# PGS_3.net
KiCad netlist of a schematic drawn in Altium Designer
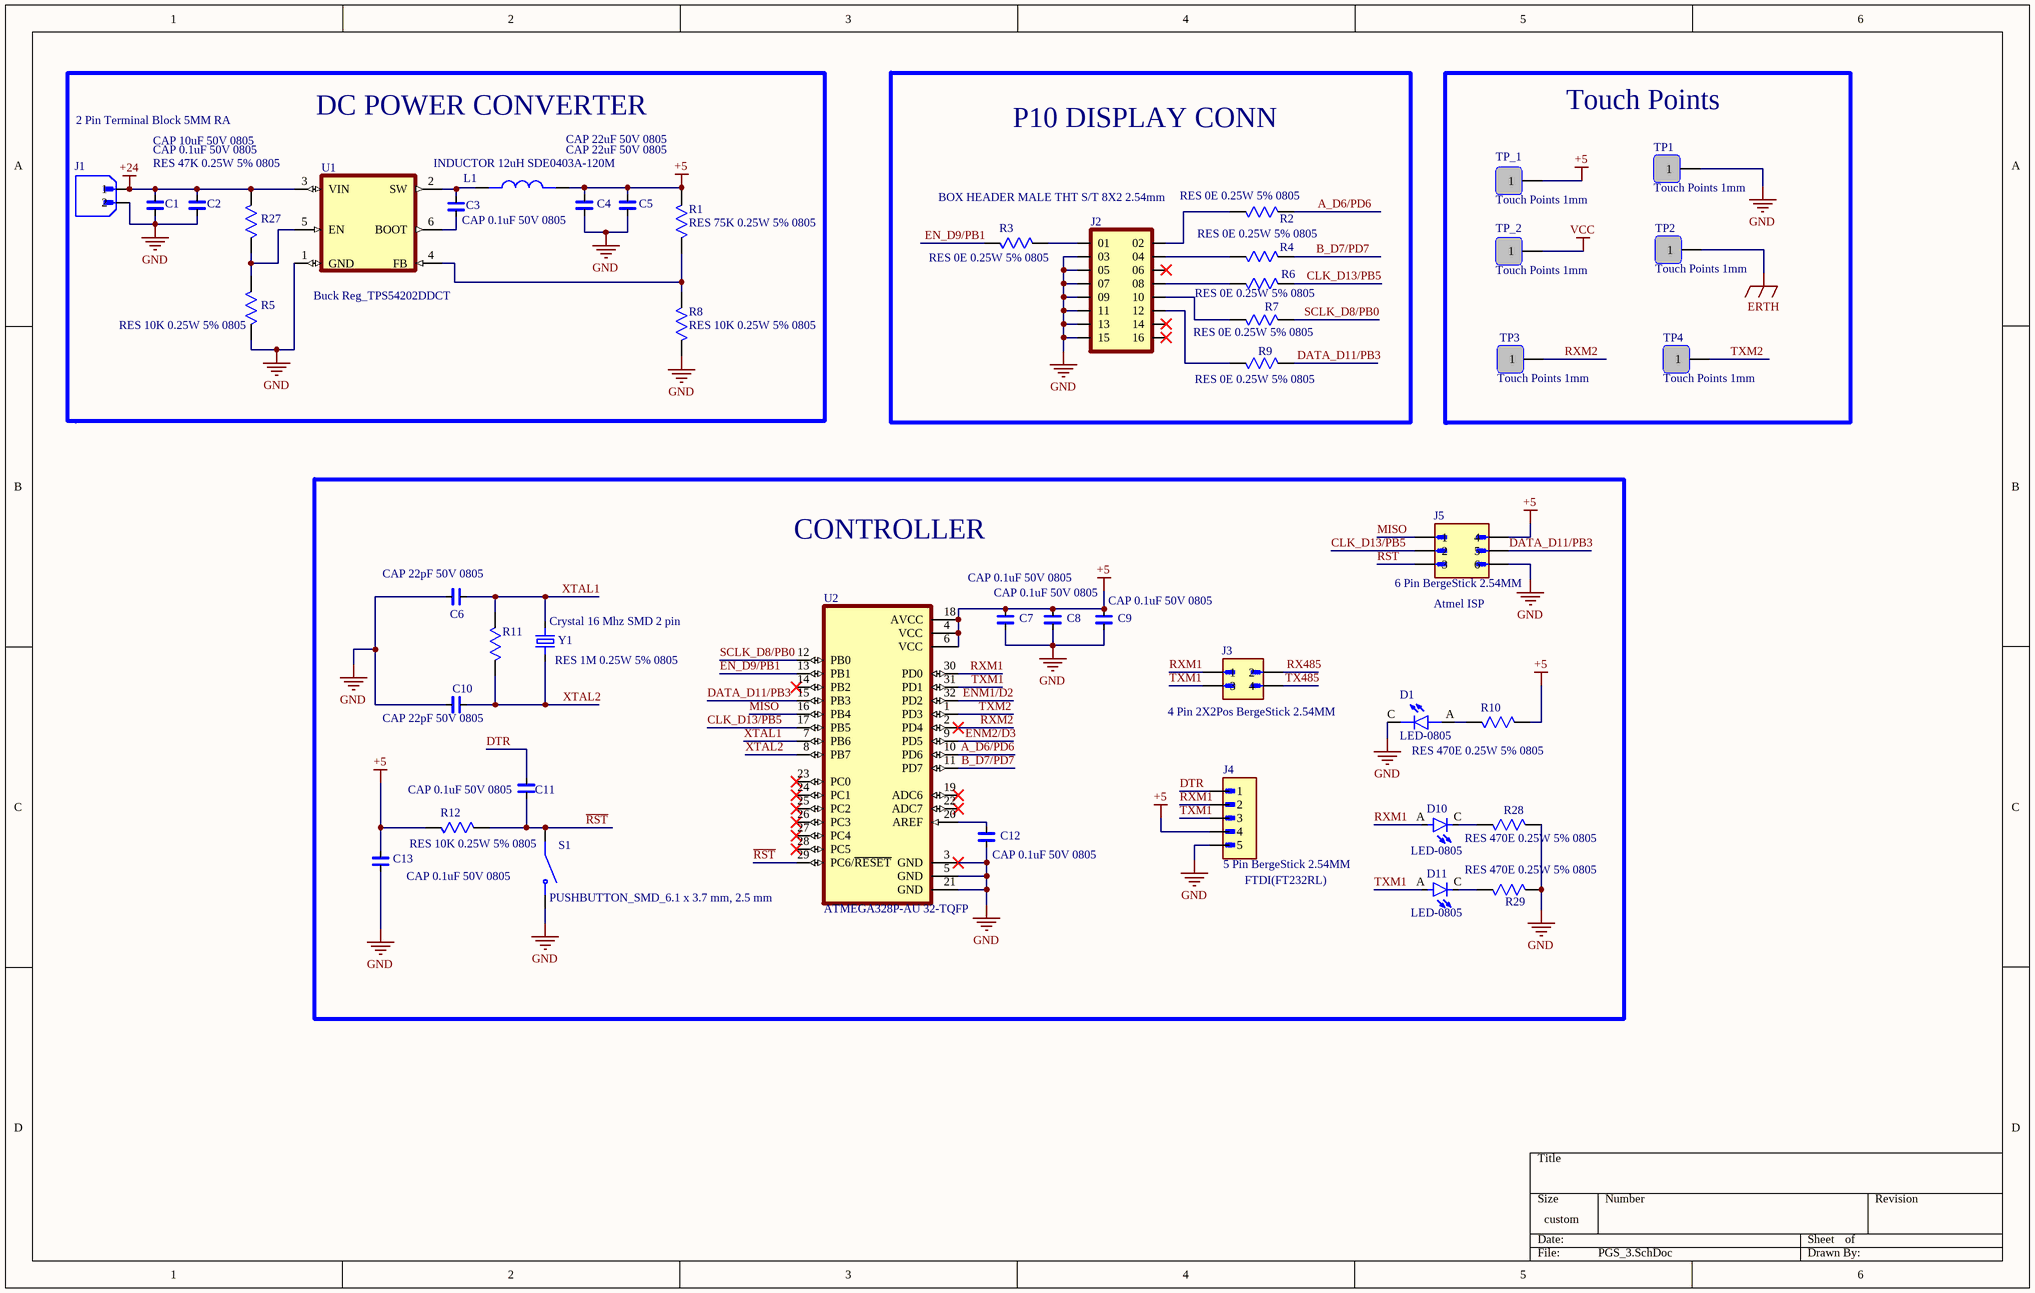
[diagram p0: PGS_3.SchDoc]

(export (version "E")
  (design (tool "Eeschema 10.0.6"))
  (components
    (comp (ref "C1")
      (value "CAP 10uF 50V 0805")
      (footprint "CAP CER 0.1uF/50V 5%")
      (description "CAP CER 0.1uF/50V  Ceramic Capacitor X7R 0805 (2012 Metric)")
      (fields (field (name "MF") "Samsung") (field (name "MP") "CL21B104KCFNNNE"))
      (libsource (lib "PGS") (part "CAP CER 0.1uF/50V 5%"))
    )
    (comp (ref "C2")
      (value "CAP 0.1uF 50V 0805")
      (footprint "CAP CER 0.1uF/50V 5%")
      (description "CAP CER 0.1uF/50V  Ceramic Capacitor X7R 0805 (2012 Metric)")
      (fields (field (name "MF") "Samsung") (field (name "MP") "CL21B104KCFNNNE"))
      (libsource (lib "PGS") (part "CAP CER 0.1uF/50V 5%"))
    )
    (comp (ref "C3")
      (value "CAP 0.1uF 50V 0805")
      (footprint "CAP CER 0.1uF/50V 5%")
      (description "CAP CER 0.1uF/50V  Ceramic Capacitor X7R 0805 (2012 Metric)")
      (fields (field (name "MF") "Samsung") (field (name "MP") "CL21B104KCFNNNE"))
      (libsource (lib "PGS") (part "CAP CER 0.1uF/50V 5%"))
    )
    (comp (ref "C4")
      (value "CAP 22uF 50V 0805")
      (footprint "CAP CER 0.1uF/50V 5%")
      (description "CAP CER 0.1uF/50V  Ceramic Capacitor X7R 0805 (2012 Metric)")
      (fields (field (name "MF") "Samsung") (field (name "MP") "CL21B104KCFNNNE"))
      (libsource (lib "PGS") (part "CAP CER 0.1uF/50V 5%"))
    )
    (comp (ref "C5")
      (value "CAP 22uF 50V 0805")
      (footprint "CAP CER 0.1uF/50V 5%")
      (description "CAP CER 0.1uF/50V  Ceramic Capacitor X7R 0805 (2012 Metric)")
      (fields (field (name "MF") "Samsung") (field (name "MP") "CL21B104KCFNNNE"))
      (libsource (lib "PGS") (part "CAP CER 0.1uF/50V 5%"))
    )
    (comp (ref "C6")
      (value "CAP 22pF 50V 0805")
      (footprint "CAP CER 0.1uF/50V 5%")
      (description "CAP CER 0.1uF/50V  Ceramic Capacitor X7R 0805 (2012 Metric)")
      (fields (field (name "MF") "Samsung") (field (name "MP") "CL21B104KCFNNNE"))
      (libsource (lib "") (part "CAP CER 0.1uF/50V 5%_1"))
    )
    (comp (ref "C7")
      (value "CAP 0.1uF 50V 0805")
      (footprint "CAP CER 0.1uF/50V 5%")
      (description "CAP CER 0.1uF/50V  Ceramic Capacitor X7R 0805 (2012 Metric)")
      (fields (field (name "MF") "Samsung") (field (name "MP") "CL21B104KCFNNNE"))
      (libsource (lib "PGS") (part "CAP CER 0.1uF/50V 5%"))
    )
    (comp (ref "C8")
      (value "CAP 0.1uF 50V 0805")
      (footprint "CAP CER 0.1uF/50V 5%")
      (description "CAP CER 0.1uF/50V  Ceramic Capacitor X7R 0805 (2012 Metric)")
      (fields (field (name "MF") "Samsung") (field (name "MP") "CL21B104KCFNNNE"))
      (libsource (lib "PGS") (part "CAP CER 0.1uF/50V 5%"))
    )
    (comp (ref "C9")
      (value "CAP 0.1uF 50V 0805")
      (footprint "CAP CER 0.1uF/50V 5%")
      (description "CAP CER 0.1uF/50V  Ceramic Capacitor X7R 0805 (2012 Metric)")
      (fields (field (name "MF") "Samsung") (field (name "MP") "CL21B104KCFNNNE"))
      (libsource (lib "PGS") (part "CAP CER 0.1uF/50V 5%"))
    )
    (comp (ref "C10")
      (value "CAP 22pF 50V 0805")
      (footprint "CAP CER 0.1uF/50V 5%")
      (description "CAP CER 0.1uF/50V  Ceramic Capacitor X7R 0805 (2012 Metric)")
      (fields (field (name "MF") "Samsung") (field (name "MP") "CL21B104KCFNNNE"))
      (libsource (lib "") (part "CAP CER 0.1uF/50V 5%_1"))
    )
    (comp (ref "C11")
      (value "CAP 0.1uF 50V 0805")
      (footprint "CAP CER 0.1uF/50V 5%")
      (description "CAP CER 0.1uF/50V  Ceramic Capacitor X7R 0805 (2012 Metric)")
      (fields (field (name "MF") "Samsung") (field (name "MP") "CL21B104KCFNNNE"))
      (libsource (lib "PGS") (part "CAP CER 0.1uF/50V 5%"))
    )
    (comp (ref "C12")
      (value "CAP 0.1uF 50V 0805")
      (footprint "CAP CER 0.1uF/50V 5%")
      (description "CAP CER 0.1uF/50V  Ceramic Capacitor X7R 0805 (2012 Metric)")
      (fields (field (name "MF") "Samsung") (field (name "MP") "CL21B104KCFNNNE"))
      (libsource (lib "PGS") (part "CAP CER 0.1uF/50V 5%"))
    )
    (comp (ref "C13")
      (value "CAP 0.1uF 50V 0805")
      (footprint "CAP CER 0.1uF/50V 5%")
      (description "CAP CER 0.1uF/50V  Ceramic Capacitor X7R 0805 (2012 Metric)")
      (fields (field (name "MF") "Samsung") (field (name "MP") "CL21B104KCFNNNE"))
      (libsource (lib "PGS") (part "CAP CER 0.1uF/50V 5%"))
    )
    (comp (ref "D1")
      (value "LED-0805")
      (footprint "LED-0805")
      (description "Red 640nm LED Indication - Discrete 1.85V 0805 (2012 Metric) APT2012SRCPRV")
      (fields (field (name "MF") "Kingbright") (field (name "MP") "APT2012SRCPRV"))
      (libsource (lib "P10_ESP32") (part "LED-0805"))
    )
    (comp (ref "D10")
      (value "LED-0805")
      (footprint "LED-0805")
      (description "Red 640nm LED Indication - Discrete 1.85V 0805 (2012 Metric) SMT APT2012SRCPRV")
      (fields (field (name "MF") "Kingbright") (field (name "MP") "APT2012SRCPRV"))
      (libsource (lib "PGS") (part "LED-0805"))
    )
    (comp (ref "D11")
      (value "LED-0805")
      (footprint "LED-0805")
      (description "Red 640nm LED Indication - Discrete 1.85V 0805 (2012 Metric) SMT APT2012SRCPRV")
      (fields (field (name "MF") "Kingbright") (field (name "MP") "APT2012SRCPRV"))
      (libsource (lib "PGS") (part "LED-0805"))
    )
    (comp (ref "J1")
      (value "2 Pin Terminal Block 5MM RA")
      (footprint "2 Pin Terminal Block 5MM RA")
      (description "2 Pin Terminal Block HDR 5MM THT RA _OQ0271510000G")
      (fields (field (name "MF") "Amphenol Anytek") (field (name "MP") "OQ0271510000G"))
      (libsource (lib "PGS") (part "2 Pin Terminal Block 5MM RA"))
    )
    (comp (ref "J2")
      (value "BOX HEADER MALE THT S/T 8X2 2.54mm")
      (footprint "BOX HEADER MALE 8X2 2.54mm")
      (description "THT BOX HEADER MALE S/T 8X2 2.54mm 16 pin")
      (fields (field (name "MP") "TSS-108-01-T-D"))
      (libsource (lib "PGS") (part "BOX HEADER MALE THT S/T 8X2 2.54mm"))
    )
    (comp (ref "J3")
      (value "4 Pin 2X2Pos BergeStick 2.54MM")
      (footprint "4 Pin BergeStick 2.54MM")
      (description "4 Pin 2X2Pos THT S/T BergeStick 2.54MM Amphenol 67997-104HLF 3A")
      (fields (field (name "MF") "Amphenol ICC") (field (name "DIGI-KEY_PART_NUMBER") "609-3225-ND"))
      (libsource (lib "PGS") (part "4 Pin 2X2Pos BergeStick 2.54MM"))
    )
    (comp (ref "J4")
      (value "5 Pin BergeStick 2.54MM")
      (footprint "5 Pin BergeStick 2.54MM")
      (description "5 Pin 5Pos THT S/T BergeStick 2.54MM Amphenol68002-405HLF 3A")
      (fields (field (name "MP") "68002-405HLF"))
      (libsource (lib "PGS") (part "5 Pin BergeStick 2.54MM"))
    )
    (comp (ref "J5")
      (value "6 Pin BergeStick 2.54MM")
      (footprint "6 Pin BergeStick 2.54MM - duplicate")
      (description "6 Pin 3X3Pos THT S/T BergeStick 2.54MM Amphenol 69192-406HLF")
      (fields (field (name "DIGI-KEY_PART_NUMBER") "609-4711-ND") (field (name "MP") "69192-406HLF"))
      (libsource (lib "PGS") (part "6 Pin BergeStick 2.54MM_1"))
    )
    (comp (ref "L1")
      (value "INDUCTOR 12uH SDE0403A-120M")
      (footprint "INDUCTOR 12uH SDE0403A-120M")
      (description "INDUCTOR_2020(5.5mmX4.5mm)  SMT INDUCTOR 12uH SDE0403A-120M0 LQH5BPB4R7NT0L")
      (fields (field (name "MP") "LQH5BPB4R7NT0L"))
      (libsource (lib "PGS") (part "INDUCTOR 12uH SDE0403A-120M"))
    )
    (comp (ref "R1")
      (value "RES 75K 0.25W 5% 0805")
      (footprint "RES 0805 10K/0.25W 5%")
      (description "RESISTOR, THICK FILM, 10K, 5%, 0805 0.25W")
      (fields (field (name "MP") "ERJ-6GEYJ103V") (field (name "MF") "Panasonic Electronic"))
      (libsource (lib "PGS") (part "RES 10K 0.25W 5% 0805"))
    )
    (comp (ref "R2")
      (value "RES 0E 0.25W 5% 0805")
      (footprint "RES 0805 10K/0.25W 5%")
      (description "RESISTOR, THICK FILM, 10K, 5%, 0805 0.25W")
      (fields (field (name "MP") "ERJ-6GEYJ103V") (field (name "MF") "Panasonic Electronic"))
      (libsource (lib "PGS") (part "RES 10K 0.25W 5% 0805"))
    )
    (comp (ref "R3")
      (value "RES 0E 0.25W 5% 0805")
      (footprint "RES 0805 10K/0.25W 5%")
      (description "RESISTOR, THICK FILM, 10K, 5%, 0805 0.25W")
      (fields (field (name "MP") "ERJ-6GEYJ103V") (field (name "MF") "Panasonic Electronic"))
      (libsource (lib "PGS") (part "RES 10K 0.25W 5% 0805"))
    )
    (comp (ref "R4")
      (value "RES 0E 0.25W 5% 0805")
      (footprint "RES 0805 10K/0.25W 5%")
      (description "RESISTOR, THICK FILM, 10K, 5%, 0805 0.25W")
      (fields (field (name "MP") "ERJ-6GEYJ103V") (field (name "MF") "Panasonic Electronic"))
      (libsource (lib "PGS") (part "RES 10K 0.25W 5% 0805"))
    )
    (comp (ref "R5")
      (value "RES 10K 0.25W 5% 0805")
      (footprint "RES 0805 10K/0.25W 5%")
      (description "RESISTOR, THICK FILM, 10K, 5%, 0805 0.25W")
      (fields (field (name "MP") "ERJ-6GEYJ103V") (field (name "MF") "Panasonic Electronic"))
      (libsource (lib "PGS") (part "RES 10K 0.25W 5% 0805"))
    )
    (comp (ref "R6")
      (value "RES 0E 0.25W 5% 0805")
      (footprint "RES 0805 10K/0.25W 5%")
      (description "RESISTOR, THICK FILM, 10K, 5%, 0805 0.25W")
      (fields (field (name "MP") "ERJ-6GEYJ103V") (field (name "MF") "Panasonic Electronic"))
      (libsource (lib "PGS") (part "RES 10K 0.25W 5% 0805"))
    )
    (comp (ref "R7")
      (value "RES 0E 0.25W 5% 0805")
      (footprint "RES 0805 10K/0.25W 5%")
      (description "RESISTOR, THICK FILM, 10K, 5%, 0805 0.25W")
      (fields (field (name "MP") "ERJ-6GEYJ103V") (field (name "MF") "Panasonic Electronic"))
      (libsource (lib "PGS") (part "RES 10K 0.25W 5% 0805"))
    )
    (comp (ref "R8")
      (value "RES 10K 0.25W 5% 0805")
      (footprint "RES 0805 10K/0.25W 5%")
      (description "RESISTOR, THICK FILM, 10K, 5%, 0805 0.25W")
      (fields (field (name "MP") "ERJ-6GEYJ103V") (field (name "MF") "Panasonic Electronic"))
      (libsource (lib "PGS") (part "RES 10K 0.25W 5% 0805"))
    )
    (comp (ref "R9")
      (value "RES 0E 0.25W 5% 0805")
      (footprint "RES 0805 10K/0.25W 5%")
      (description "RESISTOR, THICK FILM, 10K, 5%, 0805 0.25W")
      (fields (field (name "MP") "ERJ-6GEYJ103V") (field (name "MF") "Panasonic Electronic"))
      (libsource (lib "PGS") (part "RES 10K 0.25W 5% 0805"))
    )
    (comp (ref "R10")
      (value "RES 470E 0.25W 5% 0805")
      (footprint "RES 0805 10K/0.25W 5%")
      (description "RESISTOR, THICK FILM, 10K, 5%, 0805 0.25W")
      (fields (field (name "MP") "ERJ-6GEYJ103V") (field (name "MF") "Panasonic Electronic"))
      (libsource (lib "PGS") (part "RES 10K 0.25W 5% 0805"))
    )
    (comp (ref "R11")
      (value "RES 1M 0.25W 5% 0805")
      (footprint "RES 0805 10K/0.25W 5%")
      (description "RESISTOR, THICK FILM, 10K, 5%, 0805 0.25W")
      (fields (field (name "MP") "ERJ-6GEYJ103V") (field (name "MF") "Panasonic Electronic"))
      (libsource (lib "PGS") (part "RES 10K 0.25W 5% 0805"))
    )
    (comp (ref "R12")
      (value "RES 10K 0.25W 5% 0805")
      (footprint "RES 0805 10K/0.25W 5%")
      (description "RESISTOR, THICK FILM, 10K, 5%, 0805 0.25W")
      (fields (field (name "MP") "ERJ-6GEYJ103V") (field (name "MF") "Panasonic Electronic"))
      (libsource (lib "PGS") (part "RES 10K 0.25W 5% 0805"))
    )
    (comp (ref "R27")
      (value "RES 47K 0.25W 5% 0805")
      (footprint "RES 0805 10K/0.25W 5%")
      (description "RESISTOR, THICK FILM, 10K, 5%, 0805 0.25W")
      (fields (field (name "MP") "ERJ-6GEYJ103V") (field (name "MF") "Panasonic Electronic"))
      (libsource (lib "PGS") (part "RES 10K 0.25W 5% 0805"))
    )
    (comp (ref "R28")
      (value "RES 470E 0.25W 5% 0805")
      (footprint "RES 0805 10K/0.25W 5%")
      (description "RESISTOR, THICK FILM, 10K, 5%, 0805 0.25W SMT")
      (fields (field (name "MP") "ERJ-6GEYJ103V") (field (name "MF") "Panasonic Electronic"))
      (libsource (lib "PGS") (part "RES 10K 0.25W 5% 0805"))
    )
    (comp (ref "R29")
      (value "RES 470E 0.25W 5% 0805")
      (footprint "RES 0805 10K/0.25W 5%")
      (description "RESISTOR, THICK FILM, 10K, 5%, 0805 0.25W SMT")
      (fields (field (name "MP") "ERJ-6GEYJ103V") (field (name "MF") "Panasonic Electronic"))
      (libsource (lib "PGS") (part "RES 10K 0.25W 5% 0805"))
    )
    (comp (ref "S1")
      (value "PUSHBUTTON_SMD_6.1 x 3.7 mm, 2.5 mm")
      (footprint "PUSHBUTTON_SMD_6.1 x 3.7 mm, 2.5 mm")
      (fields (field (name "MF") "Same Sky") (field (name "MP") "TS09-63-25-R-260-SMT-TR"))
      (libsource (lib "P10_ATMEGA328P") (part "PUSHBUTTON_SMD_6.1 x 3.7 mm, 2.5 mm"))
    )
    (comp (ref "TP1")
      (value "Touch Points 1mm")
      (footprint "Touch Points 1mm")
      (description "Touch Points 0.75mm to1mm")
      (libsource (lib "P10_ESP32") (part "Touch Points"))
    )
    (comp (ref "TP2")
      (value "Touch Points 1mm")
      (footprint "Touch Points 1mm")
      (description "Touch Points 0.75mm to1mm")
      (libsource (lib "P10_ESP32") (part "Touch Points"))
    )
    (comp (ref "TP3")
      (value "Touch Points 1mm")
      (footprint "Touch Points 1mm")
      (description "Touch Points 0.75mm to1mm")
      (libsource (lib "P10_ESP32") (part "Touch Points"))
    )
    (comp (ref "TP4")
      (value "Touch Points 1mm")
      (footprint "Touch Points 1mm")
      (description "Touch Points 0.75mm to1mm")
      (libsource (lib "P10_ESP32") (part "Touch Points"))
    )
    (comp (ref "TP_1")
      (value "Touch Points 1mm")
      (footprint "Touch Points 1mm")
      (description "Touch Points 0.75mm to1mm")
      (libsource (lib "P10_ESP32") (part "Touch Points"))
    )
    (comp (ref "TP_2")
      (value "Touch Points 1mm")
      (footprint "Touch Points 1mm")
      (description "Touch Points 0.75mm to1mm")
      (libsource (lib "P10_ESP32") (part "Touch Points"))
    )
    (comp (ref "U1")
      (value "Buck Reg_TPS54202DDCT")
      (footprint "Buck Reg_TPS54202DDCT")
      (description "4.5V to 28V Input, 2A Output, EMI Friendly Synchronous Step-Down Converter TPS54202DDCT")
      (fields (field (name "MF") "Texas Instruments") (field (name "MP") "TPS54202DDCT"))
      (libsource (lib "PGS") (part "TPS54202DDCT"))
    )
    (comp (ref "U2")
      (value "ATMEGA328P-AU 32-TQFP")
      (footprint "ATMEGA328P-AU 32-TQFP")
      (description "AVR AVRÂ® ATmega Microcontroller IC 8-Bit 20MHz 32KB (16K x 16) FLASH 32-TQFP (7x7)")
      (fields (field (name "MF") "Microchip") (field (name "MP") "ATMEGA328P-AU"))
      (libsource (lib "PGS") (part "ATMEGA328P-AU_1"))
    )
    (comp (ref "Y1")
      (value "Crystal 16 Mhz SMD 2 pin")
      (footprint "Crystal 16 Mhz SMD 2 pin")
      (fields (field (name "MF") "Fox Electronics") (field (name "MP") "FOXSDLF/128-20"))
      (libsource (lib "PGS") (part "Crystal 16 Mhz SMD 2 pin_1"))
    )
  )
  (nets
    (net (code "1") (name "+5") (class "Default")
      (node (ref "C13") (pin "2") (pinfunction "2_2") (pintype "passive"))
      (node (ref "C4") (pin "2") (pinfunction "2_2") (pintype "passive"))
      (node (ref "C5") (pin "2") (pinfunction "2_2") (pintype "passive"))
      (node (ref "C7") (pin "2") (pinfunction "2_2") (pintype "passive"))
      (node (ref "C8") (pin "2") (pinfunction "2_2") (pintype "passive"))
      (node (ref "C9") (pin "2") (pinfunction "2_2") (pintype "passive"))
      (node (ref "J4") (pin "4") (pinfunction "4_4") (pintype "passive"))
      (node (ref "J5") (pin "4") (pinfunction "4_4") (pintype "passive"))
      (node (ref "L1") (pin "2") (pinfunction "2_2") (pintype "passive"))
      (node (ref "R1") (pin "2") (pinfunction "2_2") (pintype "passive"))
      (node (ref "R10") (pin "2") (pinfunction "2_2") (pintype "passive"))
      (node (ref "R12") (pin "1") (pinfunction "1_1") (pintype "passive"))
      (node (ref "TP_1") (pin "1") (pinfunction "1_1") (pintype "passive"))
      (node (ref "U2") (pin "18") (pinfunction "AVCC_18") (pintype "power_in"))
      (node (ref "U2") (pin "4") (pinfunction "VCC_4") (pintype "power_in"))
      (node (ref "U2") (pin "6") (pinfunction "VCC_6") (pintype "power_in"))
    )
    (net (code "2") (name "+24") (class "Default")
      (node (ref "C1") (pin "2") (pinfunction "2_2") (pintype "passive"))
      (node (ref "C2") (pin "2") (pinfunction "2_2") (pintype "passive"))
      (node (ref "J1") (pin "1") (pinfunction "1_1") (pintype "passive"))
      (node (ref "R27") (pin "2") (pinfunction "2_2") (pintype "passive"))
      (node (ref "U1") (pin "3") (pinfunction "VIN_3") (pintype "bidirectional"))
    )
    (net (code "3") (name "/A_D6{slash}PD6") (class "Default")
      (node (ref "R2") (pin "2") (pinfunction "2_2") (pintype "passive"))
      (node (ref "U2") (pin "10") (pinfunction "PD6_10") (pintype "bidirectional"))
    )
    (net (code "4") (name "/B_D7{slash}PD7") (class "Default")
      (node (ref "R4") (pin "2") (pinfunction "2_2") (pintype "passive"))
      (node (ref "U2") (pin "11") (pinfunction "PD7_11") (pintype "bidirectional"))
    )
    (net (code "5") (name "/CLK_D13{slash}PB5") (class "Default")
      (node (ref "J5") (pin "2") (pinfunction "2_2") (pintype "passive"))
      (node (ref "R6") (pin "2") (pinfunction "2_2") (pintype "passive"))
      (node (ref "U2") (pin "17") (pinfunction "PB5_17") (pintype "bidirectional"))
    )
    (net (code "6") (name "/DATA_D11{slash}PB3") (class "Default")
      (node (ref "J5") (pin "5") (pinfunction "5_5") (pintype "passive"))
      (node (ref "R9") (pin "2") (pinfunction "2_2") (pintype "passive"))
      (node (ref "U2") (pin "15") (pinfunction "PB3_15") (pintype "bidirectional"))
    )
    (net (code "7") (name "/DTR") (class "Default")
      (node (ref "C11") (pin "2") (pinfunction "2_2") (pintype "passive"))
      (node (ref "J4") (pin "1") (pinfunction "1_1") (pintype "passive"))
    )
    (net (code "8") (name "/ENM1{slash}D2") (class "Default")
      (node (ref "U2") (pin "32") (pinfunction "PD2_32") (pintype "bidirectional"))
    )
    (net (code "9") (name "/ENM2{slash}D3") (class "Default")
      (node (ref "U2") (pin "9") (pinfunction "PD5_9") (pintype "bidirectional"))
    )
    (net (code "10") (name "/EN_D9{slash}PB1") (class "Default")
      (node (ref "R3") (pin "1") (pinfunction "1_1") (pintype "passive"))
      (node (ref "U2") (pin "13") (pinfunction "PB1_13") (pintype "bidirectional"))
    )
    (net (code "11") (name "/MISO") (class "Default")
      (node (ref "J5") (pin "1") (pinfunction "1_1") (pintype "passive"))
      (node (ref "U2") (pin "16") (pinfunction "PB4_16") (pintype "bidirectional"))
    )
    (net (code "12") (name "/RX485") (class "Default")
      (node (ref "J3") (pin "2") (pinfunction "2_2") (pintype "passive"))
    )
    (net (code "13") (name "/RXM1") (class "Default")
      (node (ref "D10") (pin "A") (pinfunction "A_A") (pintype "passive"))
      (node (ref "J3") (pin "1") (pinfunction "1_1") (pintype "passive"))
      (node (ref "J4") (pin "2") (pinfunction "2_2") (pintype "passive"))
      (node (ref "U2") (pin "30") (pinfunction "PD0_30") (pintype "bidirectional"))
    )
    (net (code "14") (name "/RXM2") (class "Default")
      (node (ref "TP3") (pin "1") (pinfunction "1_1") (pintype "passive"))
      (node (ref "U2") (pin "2") (pinfunction "PD4_2") (pintype "bidirectional"))
    )
    (net (code "15") (name "/SCLK_D8{slash}PB0") (class "Default")
      (node (ref "R7") (pin "2") (pinfunction "2_2") (pintype "passive"))
      (node (ref "U2") (pin "12") (pinfunction "PB0_12") (pintype "bidirectional"))
    )
    (net (code "16") (name "/TX485") (class "Default")
      (node (ref "J3") (pin "4") (pinfunction "4_4") (pintype "passive"))
    )
    (net (code "17") (name "/TXM1") (class "Default")
      (node (ref "D11") (pin "A") (pinfunction "A_A") (pintype "passive"))
      (node (ref "J3") (pin "3") (pinfunction "3_3") (pintype "passive"))
      (node (ref "J4") (pin "3") (pinfunction "3_3") (pintype "passive"))
      (node (ref "U2") (pin "31") (pinfunction "PD1_31") (pintype "bidirectional"))
    )
    (net (code "18") (name "/TXM2") (class "Default")
      (node (ref "TP4") (pin "1") (pinfunction "1_1") (pintype "passive"))
      (node (ref "U2") (pin "1") (pinfunction "PD3_1") (pintype "bidirectional"))
    )
    (net (code "19") (name "/XTAL1") (class "Default")
      (node (ref "C6") (pin "2") (pinfunction "2_2") (pintype "passive"))
      (node (ref "R11") (pin "2") (pinfunction "2_2") (pintype "passive"))
      (node (ref "U2") (pin "7") (pinfunction "PB6_7") (pintype "bidirectional"))
      (node (ref "Y1") (pin "2") (pinfunction "2_2") (pintype "passive"))
    )
    (net (code "20") (name "/XTAL2") (class "Default")
      (node (ref "C10") (pin "2") (pinfunction "2_2") (pintype "passive"))
      (node (ref "R11") (pin "1") (pinfunction "1_1") (pintype "passive"))
      (node (ref "U2") (pin "8") (pinfunction "PB7_8") (pintype "bidirectional"))
      (node (ref "Y1") (pin "1") (pinfunction "1_1") (pintype "passive"))
    )
    (net (code "21") (name "/~{RST}") (class "Default")
      (node (ref "C11") (pin "1") (pinfunction "1_1") (pintype "passive"))
      (node (ref "J5") (pin "3") (pinfunction "3_3") (pintype "passive"))
      (node (ref "R12") (pin "2") (pinfunction "2_2") (pintype "passive"))
      (node (ref "S1") (pin "1") (pinfunction "1_1") (pintype "passive"))
      (node (ref "U2") (pin "29") (pinfunction "PC6/~{RESET}_29") (pintype "bidirectional"))
    )
    (net (code "22") (name "ERTH") (class "Default")
      (node (ref "TP2") (pin "1") (pinfunction "1_1") (pintype "passive"))
    )
    (net (code "23") (name "GND") (class "Default")
      (node (ref "C1") (pin "1") (pinfunction "1_1") (pintype "passive"))
      (node (ref "C10") (pin "1") (pinfunction "1_1") (pintype "passive"))
      (node (ref "C12") (pin "1") (pinfunction "1_1") (pintype "passive"))
      (node (ref "C13") (pin "1") (pinfunction "1_1") (pintype "passive"))
      (node (ref "C2") (pin "1") (pinfunction "1_1") (pintype "passive"))
      (node (ref "C4") (pin "1") (pinfunction "1_1") (pintype "passive"))
      (node (ref "C5") (pin "1") (pinfunction "1_1") (pintype "passive"))
      (node (ref "C6") (pin "1") (pinfunction "1_1") (pintype "passive"))
      (node (ref "C7") (pin "1") (pinfunction "1_1") (pintype "passive"))
      (node (ref "C8") (pin "1") (pinfunction "1_1") (pintype "passive"))
      (node (ref "C9") (pin "1") (pinfunction "1_1") (pintype "passive"))
      (node (ref "D1") (pin "C") (pinfunction "C_C") (pintype "passive"))
      (node (ref "J1") (pin "2") (pinfunction "2_2") (pintype "passive"))
      (node (ref "J2") (pin "03") (pinfunction "03_03") (pintype "passive"))
      (node (ref "J2") (pin "05") (pinfunction "05_05") (pintype "passive"))
      (node (ref "J2") (pin "07") (pinfunction "07_07") (pintype "passive"))
      (node (ref "J2") (pin "09") (pinfunction "09_09") (pintype "passive"))
      (node (ref "J2") (pin "11") (pinfunction "11_11") (pintype "passive"))
      (node (ref "J2") (pin "13") (pinfunction "13_13") (pintype "passive"))
      (node (ref "J2") (pin "15") (pinfunction "15_15") (pintype "passive"))
      (node (ref "J4") (pin "5") (pinfunction "5_5") (pintype "passive"))
      (node (ref "J5") (pin "6") (pinfunction "6_6") (pintype "passive"))
      (node (ref "R28") (pin "2") (pinfunction "2_2") (pintype "passive"))
      (node (ref "R29") (pin "2") (pinfunction "2_2") (pintype "passive"))
      (node (ref "R5") (pin "1") (pinfunction "1_1") (pintype "passive"))
      (node (ref "R8") (pin "1") (pinfunction "1_1") (pintype "passive"))
      (node (ref "S1") (pin "2") (pinfunction "2_2") (pintype "passive"))
      (node (ref "TP1") (pin "1") (pinfunction "1_1") (pintype "passive"))
      (node (ref "U1") (pin "1") (pinfunction "GND_1") (pintype "bidirectional"))
      (node (ref "U2") (pin "21") (pinfunction "GND_21") (pintype "power_in"))
      (node (ref "U2") (pin "3") (pinfunction "GND_3") (pintype "power_in"))
      (node (ref "U2") (pin "5") (pinfunction "GND_5") (pintype "power_in"))
    )
    (net (code "24") (name "Net-(D1-PadA)") (class "Default")
      (node (ref "D1") (pin "A") (pinfunction "A_A") (pintype "passive"))
      (node (ref "R10") (pin "1") (pinfunction "1_1") (pintype "passive"))
    )
    (net (code "25") (name "Net-(D10-PadC)") (class "Default")
      (node (ref "D10") (pin "C") (pinfunction "C_C") (pintype "passive"))
      (node (ref "R28") (pin "1") (pinfunction "1_1") (pintype "passive"))
    )
    (net (code "26") (name "Net-(D11-PadC)") (class "Default")
      (node (ref "D11") (pin "C") (pinfunction "C_C") (pintype "passive"))
      (node (ref "R29") (pin "1") (pinfunction "1_1") (pintype "passive"))
    )
    (net (code "27") (name "Net-(J2-Pad01)") (class "Default")
      (node (ref "J2") (pin "01") (pinfunction "01_01") (pintype "passive"))
      (node (ref "R3") (pin "2") (pinfunction "2_2") (pintype "passive"))
    )
    (net (code "28") (name "Net-(J2-Pad02)") (class "Default")
      (node (ref "J2") (pin "02") (pinfunction "02_02") (pintype "passive"))
      (node (ref "R2") (pin "1") (pinfunction "1_1") (pintype "passive"))
    )
    (net (code "29") (name "Net-(J2-Pad04)") (class "Default")
      (node (ref "J2") (pin "04") (pinfunction "04_04") (pintype "passive"))
      (node (ref "R4") (pin "1") (pinfunction "1_1") (pintype "passive"))
    )
    (net (code "30") (name "Net-(J2-Pad08)") (class "Default")
      (node (ref "J2") (pin "08") (pinfunction "08_08") (pintype "passive"))
      (node (ref "R6") (pin "1") (pinfunction "1_1") (pintype "passive"))
    )
    (net (code "31") (name "Net-(J2-Pad10)") (class "Default")
      (node (ref "J2") (pin "10") (pinfunction "10_10") (pintype "passive"))
      (node (ref "R7") (pin "1") (pinfunction "1_1") (pintype "passive"))
    )
    (net (code "32") (name "Net-(J2-Pad12)") (class "Default")
      (node (ref "J2") (pin "12") (pinfunction "12_12") (pintype "passive"))
      (node (ref "R9") (pin "1") (pinfunction "1_1") (pintype "passive"))
    )
    (net (code "33") (name "Net-(U1-BOOT)") (class "Default")
      (node (ref "C3") (pin "1") (pinfunction "1_1") (pintype "passive"))
      (node (ref "U1") (pin "6") (pinfunction "BOOT_6") (pintype "output"))
    )
    (net (code "34") (name "Net-(U1-EN)") (class "Default")
      (node (ref "R27") (pin "1") (pinfunction "1_1") (pintype "passive"))
      (node (ref "R5") (pin "2") (pinfunction "2_2") (pintype "passive"))
      (node (ref "U1") (pin "5") (pinfunction "EN_5") (pintype "input"))
    )
    (net (code "35") (name "Net-(U1-FB)") (class "Default")
      (node (ref "R1") (pin "1") (pinfunction "1_1") (pintype "passive"))
      (node (ref "R8") (pin "2") (pinfunction "2_2") (pintype "passive"))
      (node (ref "U1") (pin "4") (pinfunction "FB_4") (pintype "input"))
    )
    (net (code "36") (name "Net-(U1-SW)") (class "Default")
      (node (ref "C3") (pin "2") (pinfunction "2_2") (pintype "passive"))
      (node (ref "L1") (pin "1") (pinfunction "1_1") (pintype "passive"))
      (node (ref "U1") (pin "2") (pinfunction "SW_2") (pintype "output"))
    )
    (net (code "37") (name "Net-(U2-AREF)") (class "Default")
      (node (ref "C12") (pin "2") (pinfunction "2_2") (pintype "passive"))
      (node (ref "U2") (pin "20") (pinfunction "AREF_20") (pintype "input"))
    )
    (net (code "38") (name "VCC") (class "Default")
      (node (ref "TP_2") (pin "1") (pinfunction "1_1") (pintype "passive"))
    )
    (net (code "39") (name "unconnected-(J2-Pad06)") (class "Default")
      (node (ref "J2") (pin "06") (pinfunction "06_06") (pintype "passive+no_connect"))
    )
    (net (code "40") (name "unconnected-(J2-Pad14)") (class "Default")
      (node (ref "J2") (pin "14") (pinfunction "14_14") (pintype "passive+no_connect"))
    )
    (net (code "41") (name "unconnected-(J2-Pad16)") (class "Default")
      (node (ref "J2") (pin "16") (pinfunction "16_16") (pintype "passive+no_connect"))
    )
    (net (code "42") (name "unconnected-(U2-ADC6-Pad19)") (class "Default")
      (node (ref "U2") (pin "19") (pinfunction "ADC6_19") (pintype "bidirectional+no_connect"))
    )
    (net (code "43") (name "unconnected-(U2-ADC7-Pad22)") (class "Default")
      (node (ref "U2") (pin "22") (pinfunction "ADC7_22") (pintype "bidirectional+no_connect"))
    )
    (net (code "44") (name "unconnected-(U2-PB2-Pad14)") (class "Default")
      (node (ref "U2") (pin "14") (pinfunction "PB2_14") (pintype "bidirectional+no_connect"))
    )
    (net (code "45") (name "unconnected-(U2-PC0-Pad23)") (class "Default")
      (node (ref "U2") (pin "23") (pinfunction "PC0_23") (pintype "bidirectional+no_connect"))
    )
    (net (code "46") (name "unconnected-(U2-PC1-Pad24)") (class "Default")
      (node (ref "U2") (pin "24") (pinfunction "PC1_24") (pintype "bidirectional+no_connect"))
    )
    (net (code "47") (name "unconnected-(U2-PC2-Pad25)") (class "Default")
      (node (ref "U2") (pin "25") (pinfunction "PC2_25") (pintype "bidirectional+no_connect"))
    )
    (net (code "48") (name "unconnected-(U2-PC3-Pad26)") (class "Default")
      (node (ref "U2") (pin "26") (pinfunction "PC3_26") (pintype "bidirectional+no_connect"))
    )
    (net (code "49") (name "unconnected-(U2-PC4-Pad27)") (class "Default")
      (node (ref "U2") (pin "27") (pinfunction "PC4_27") (pintype "bidirectional+no_connect"))
    )
    (net (code "50") (name "unconnected-(U2-PC5-Pad28)") (class "Default")
      (node (ref "U2") (pin "28") (pinfunction "PC5_28") (pintype "bidirectional+no_connect"))
    )
  )
)
